# RS485.net
KiCad netlist of a schematic drawn in Altium Designer
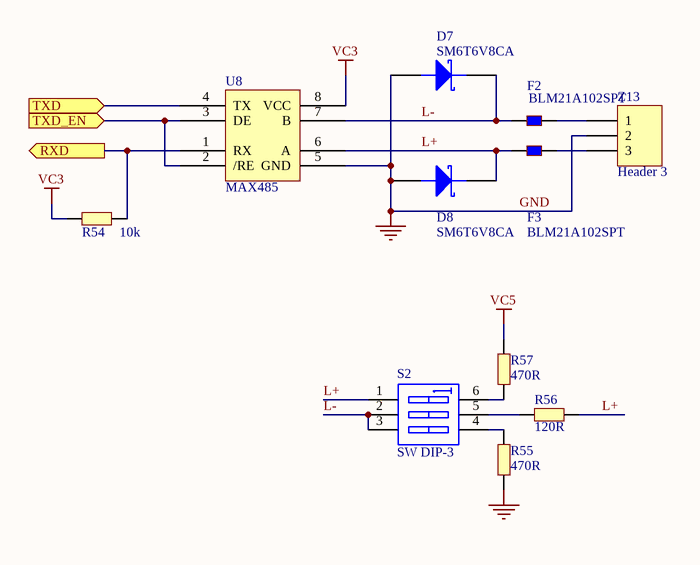
[diagram p0: RS485.SchDoc]

(export (version "E")
  (design (tool "Eeschema 10.0.6"))
  (components
    (comp (ref "D7")
      (value "SM6T6V8CA")
      (footprint "RD5_U")
      (description "Schottky Diode")
      (libsource (lib "*") (part "DIODE SCHOTTKY"))
    )
    (comp (ref "D8")
      (value "SM6T6V8CA")
      (footprint "RD5_U")
      (description "Schottky Diode")
      (libsource (lib "*") (part "DIODE SCHOTTKY"))
    )
    (comp (ref "F2")
      (value "BLM21A102SPT")
      (footprint "0805")
      (description "Koralik ferrytowy")
      (libsource (lib "*") (part "KORALIK"))
    )
    (comp (ref "F3")
      (value "BLM21A102SPT")
      (footprint "0805")
      (description "Koralik ferrytowy")
      (libsource (lib "*") (part "KORALIK"))
    )
    (comp (ref "R54") (value "10k") (footprint "0805R") (libsource (lib "*") (part "RES3")))
    (comp (ref "R55") (value "470R") (footprint "1206") (libsource (lib "") (part "RES3_1")))
    (comp (ref "R56") (value "120R") (footprint "1206") (libsource (lib "") (part "RES3_2")))
    (comp (ref "R57") (value "470R") (footprint "1206") (libsource (lib "*") (part "RES3")))
    (comp (ref "S2")
      (value "SW DIP-3")
      (footprint "DIP-6")
      (description "DIP Switch, 3 Position, SPST")
      (fields (field (name "PUBLISHER") "Altium Limited"))
      (libsource (lib "Miscellaneous Devices") (part "SW DIP-3"))
    )
    (comp (ref "U8") (value "MAX485") (footprint "SO8") (libsource (lib "*") (part "MAX485_1")))
    (comp (ref "Z13")
      (value "Header 3")
      (footprint "ARC-L-3-3.5")
      (description "Header, 3-Pin")
      (fields (field (name "PUBLISHER") "Altium Limited"))
      (libsource (lib "Miscellaneous Connectors") (part "Header 3"))
    )
  )
  (nets
    (net (code "1") (name "/L+") (class "Default")
      (node (ref "D8") (pin "K") (pinfunction "K_K") (pintype "passive"))
      (node (ref "F3") (pin "1") (pintype "passive"))
      (node (ref "R56") (pin "2") (pintype "passive"))
      (node (ref "S2") (pin "1") (pinfunction "A1_1") (pintype "passive"))
      (node (ref "U8") (pin "6") (pinfunction "A_6") (pintype "passive"))
    )
    (net (code "2") (name "/L-") (class "Default")
      (node (ref "D7") (pin "K") (pinfunction "K_K") (pintype "passive"))
      (node (ref "F2") (pin "1") (pintype "passive"))
      (node (ref "S2") (pin "2") (pinfunction "A2_2") (pintype "passive"))
      (node (ref "S2") (pin "3") (pinfunction "A3_3") (pintype "passive"))
      (node (ref "U8") (pin "7") (pinfunction "B_7") (pintype "passive"))
    )
    (net (code "3") (name "/RXD") (class "Default")
      (node (ref "R54") (pin "2") (pintype "passive"))
      (node (ref "U8") (pin "1") (pinfunction "RX_1") (pintype "passive"))
    )
    (net (code "4") (name "/TXD") (class "Default")
      (node (ref "U8") (pin "4") (pinfunction "TX_4") (pintype "passive"))
    )
    (net (code "5") (name "/TXD_EN") (class "Default")
      (node (ref "U8") (pin "2") (pinfunction "/RE_2") (pintype "passive"))
      (node (ref "U8") (pin "3") (pinfunction "DE_3") (pintype "passive"))
    )
    (net (code "6") (name "GND") (class "Default")
      (node (ref "D7") (pin "A") (pinfunction "A_A") (pintype "passive"))
      (node (ref "D8") (pin "A") (pinfunction "A_A") (pintype "passive"))
      (node (ref "R55") (pin "2") (pintype "passive"))
      (node (ref "U8") (pin "5") (pinfunction "GND_5") (pintype "passive"))
      (node (ref "Z13") (pin "2") (pinfunction "2_2") (pintype "passive"))
    )
    (net (code "7") (name "Net-(F2-Pad2)") (class "Default")
      (node (ref "F2") (pin "2") (pintype "passive"))
      (node (ref "Z13") (pin "1") (pinfunction "1_1") (pintype "passive"))
    )
    (net (code "8") (name "Net-(F3-Pad2)") (class "Default")
      (node (ref "F3") (pin "2") (pintype "passive"))
      (node (ref "Z13") (pin "3") (pinfunction "3_3") (pintype "passive"))
    )
    (net (code "9") (name "Net-(S2-B1)") (class "Default")
      (node (ref "R57") (pin "1") (pintype "passive"))
      (node (ref "S2") (pin "6") (pinfunction "B1_6") (pintype "passive"))
    )
    (net (code "10") (name "Net-(S2-B2)") (class "Default")
      (node (ref "R56") (pin "1") (pintype "passive"))
      (node (ref "S2") (pin "5") (pinfunction "B2_5") (pintype "passive"))
    )
    (net (code "11") (name "Net-(S2-B3)") (class "Default")
      (node (ref "R55") (pin "1") (pintype "passive"))
      (node (ref "S2") (pin "4") (pinfunction "B3_4") (pintype "passive"))
    )
    (net (code "12") (name "VC3") (class "Default")
      (node (ref "R54") (pin "1") (pintype "passive"))
      (node (ref "U8") (pin "8") (pinfunction "VCC_8") (pintype "passive"))
    )
    (net (code "13") (name "VC5") (class "Default") (node (ref "R57") (pin "2") (pintype "passive")))
  )
)
